# phMeter_v4_2.net
KiCad netlist of a schematic drawn in EAGLE
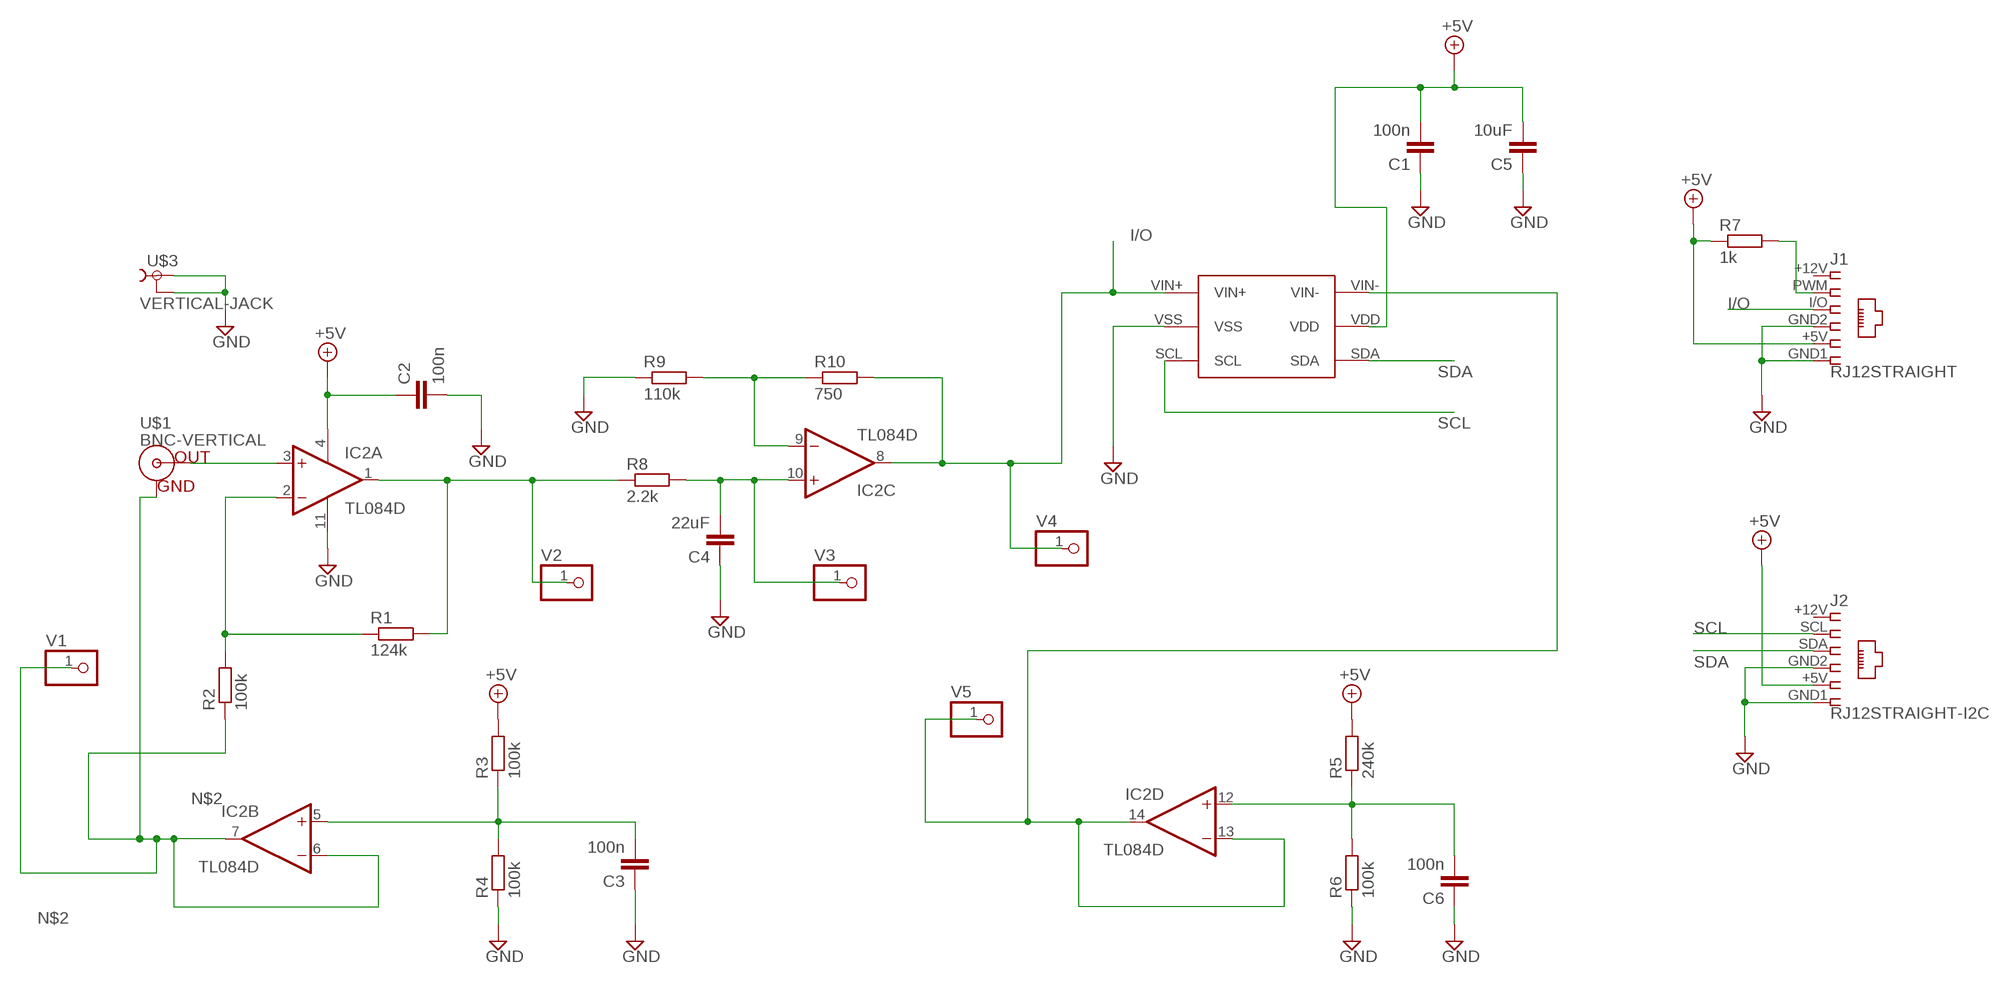
[diagram p0: schematic, sheet 1]

(export (version "E")
  (design (tool "Eeschema 10.0.6"))
  (components
    (comp (ref "C1")
      (value "100n")
      (footprint "eagle-import:C1206")
      (libsource (lib "eagle-import") (part "C-EUC1206"))
    )
    (comp (ref "C2")
      (value "100n")
      (footprint "eagle-import:C1206")
      (libsource (lib "eagle-import") (part "C-EUC1206"))
    )
    (comp (ref "C3")
      (value "100n")
      (footprint "eagle-import:C1206")
      (libsource (lib "eagle-import") (part "C-EUC1206"))
    )
    (comp (ref "C4")
      (value "22uF")
      (footprint "eagle-import:C1206")
      (libsource (lib "eagle-import") (part "C-EUC1206"))
    )
    (comp (ref "C5")
      (value "10uF")
      (footprint "eagle-import:C1206")
      (libsource (lib "eagle-import") (part "C-EUC1206"))
    )
    (comp (ref "C6")
      (value "100n")
      (footprint "eagle-import:C1206")
      (libsource (lib "eagle-import") (part "C-EUC1206"))
    )
    (comp (ref "IC2")
      (value "TL084D")
      (footprint "eagle-import:SO14")
      (libsource (lib "eagle-import") (part "TL084D"))
    )
    (comp (ref "J1")
      (value "RJ12STRAIGHT")
      (footprint "eagle-import:RJ12-STRAIGHT")
      (libsource (lib "eagle-import") (part "RJ12STRAIGHT"))
    )
    (comp (ref "J2")
      (value "RJ12STRAIGHT-I2C")
      (footprint "eagle-import:RJ12-STRAIGHT-I2C")
      (libsource (lib "eagle-import") (part "RJ12STRAIGHT-I2C"))
    )
    (comp (ref "R1")
      (value "124k")
      (footprint "eagle-import:R1206")
      (libsource (lib "eagle-import") (part "R-EU_R1206"))
    )
    (comp (ref "R2")
      (value "100k")
      (footprint "eagle-import:R1206")
      (libsource (lib "eagle-import") (part "R-EU_R1206"))
    )
    (comp (ref "R3")
      (value "100k")
      (footprint "eagle-import:R1206")
      (libsource (lib "eagle-import") (part "R-EU_R1206"))
    )
    (comp (ref "R4")
      (value "100k")
      (footprint "eagle-import:R1206")
      (libsource (lib "eagle-import") (part "R-EU_R1206"))
    )
    (comp (ref "R5")
      (value "240k")
      (footprint "eagle-import:R1206")
      (libsource (lib "eagle-import") (part "R-EU_R1206"))
    )
    (comp (ref "R6")
      (value "100k")
      (footprint "eagle-import:R1206")
      (libsource (lib "eagle-import") (part "R-EU_R1206"))
    )
    (comp (ref "R7")
      (value "1k")
      (footprint "eagle-import:R1206")
      (libsource (lib "eagle-import") (part "R-EU_R1206"))
    )
    (comp (ref "R8")
      (value "2.2k")
      (footprint "eagle-import:R1206")
      (libsource (lib "eagle-import") (part "R-EU_R1206"))
    )
    (comp (ref "R9")
      (value "110k")
      (footprint "eagle-import:R1206")
      (libsource (lib "eagle-import") (part "R-EU_R1206"))
    )
    (comp (ref "R10")
      (value "750")
      (footprint "eagle-import:R1206")
      (libsource (lib "eagle-import") (part "R-EU_R1206"))
    )
    (comp (ref "U$1")
      (value "BNC-VERTICAL")
      (footprint "eagle-import:BNC-VERTICAL")
      (libsource (lib "eagle-import") (part "BNC-VERTICAL"))
    )
    (comp (ref "U$3")
      (value "VERTICAL-JACK")
      (footprint "eagle-import:VERTICAL-JACK")
      (libsource (lib "eagle-import") (part "VERTICAL-JACK"))
    )
    (comp (ref "U$5")
      (value "MCP3425")
      (footprint "eagle-import:SOT-23-6")
      (libsource (lib "eagle-import") (part "MCP3425"))
    )
    (comp (ref "V1")
      (value "PINHD-1X1")
      (footprint "eagle-import:1X01")
      (libsource (lib "eagle-import") (part "PINHD-1X1"))
    )
    (comp (ref "V2")
      (value "PINHD-1X1")
      (footprint "eagle-import:1X01")
      (libsource (lib "eagle-import") (part "PINHD-1X1"))
    )
    (comp (ref "V3")
      (value "PINHD-1X1")
      (footprint "eagle-import:1X01")
      (libsource (lib "eagle-import") (part "PINHD-1X1"))
    )
    (comp (ref "V4")
      (value "PINHD-1X1")
      (footprint "eagle-import:1X01")
      (libsource (lib "eagle-import") (part "PINHD-1X1"))
    )
    (comp (ref "V5")
      (value "PINHD-1X1")
      (footprint "eagle-import:1X01")
      (libsource (lib "eagle-import") (part "PINHD-1X1"))
    )
  )
  (nets
    (net (code "1") (name "+5V") (class "Default")
      (node (ref "C1") (pin "2") (pinfunction "2_2") (pintype "passive"))
      (node (ref "C2") (pin "1") (pinfunction "1_1") (pintype "passive"))
      (node (ref "C5") (pin "2") (pinfunction "2_2") (pintype "passive"))
      (node (ref "IC2") (pin "4") (pinfunction "V+_4") (pintype "power_in"))
      (node (ref "J1") (pin "+5V") (pinfunction "5_+5V") (pintype "bidirectional"))
      (node (ref "J2") (pin "+5V") (pinfunction "5_+5V") (pintype "bidirectional"))
      (node (ref "R3") (pin "2") (pinfunction "2_2") (pintype "passive"))
      (node (ref "R5") (pin "2") (pinfunction "2_2") (pintype "passive"))
      (node (ref "R7") (pin "1") (pinfunction "1_1") (pintype "passive"))
      (node (ref "U$5") (pin "VDD") (pinfunction "VDD_VDD") (pintype "bidirectional"))
    )
    (net (code "2") (name "/I{slash}O") (class "Default")
      (node (ref "IC2") (pin "8") (pinfunction "OUT_8") (pintype "output"))
      (node (ref "J1") (pin "I/O") (pinfunction "3_I/O") (pintype "bidirectional"))
      (node (ref "R10") (pin "2") (pinfunction "2_2") (pintype "passive"))
      (node (ref "U$5") (pin "VIN+") (pinfunction "VIN+_VIN+") (pintype "bidirectional"))
      (node (ref "V4") (pin "1") (pinfunction "1_1") (pintype "passive"))
    )
    (net (code "3") (name "/N$2") (class "Default")
      (node (ref "IC2") (pin "6") (pinfunction "-IN_6") (pintype "input"))
      (node (ref "IC2") (pin "7") (pinfunction "OUT_7") (pintype "output"))
      (node (ref "R2") (pin "1") (pinfunction "1_1") (pintype "passive"))
      (node (ref "U$1") (pin "G") (pinfunction "GND_G") (pintype "bidirectional"))
      (node (ref "V1") (pin "1") (pinfunction "1_1") (pintype "passive"))
    )
    (net (code "4") (name "/SCL") (class "Default")
      (node (ref "J2") (pin "SCL") (pinfunction "2_SCL") (pintype "bidirectional"))
      (node (ref "U$5") (pin "SCL") (pinfunction "SCL_SCL") (pintype "bidirectional"))
    )
    (net (code "5") (name "/SDA") (class "Default")
      (node (ref "J2") (pin "SDA") (pinfunction "3_SDA") (pintype "bidirectional"))
      (node (ref "U$5") (pin "SDA") (pinfunction "SDA_SDA") (pintype "bidirectional"))
    )
    (net (code "6") (name "GND") (class "Default")
      (node (ref "C1") (pin "1") (pinfunction "1_1") (pintype "passive"))
      (node (ref "C2") (pin "2") (pinfunction "2_2") (pintype "passive"))
      (node (ref "C3") (pin "1") (pinfunction "1_1") (pintype "passive"))
      (node (ref "C4") (pin "1") (pinfunction "1_1") (pintype "passive"))
      (node (ref "C5") (pin "1") (pinfunction "1_1") (pintype "passive"))
      (node (ref "C6") (pin "1") (pinfunction "1_1") (pintype "passive"))
      (node (ref "IC2") (pin "11") (pinfunction "V-_11") (pintype "power_in"))
      (node (ref "J1") (pin "GND1") (pinfunction "6_GND1") (pintype "bidirectional"))
      (node (ref "J1") (pin "GND2") (pinfunction "4_GND2") (pintype "bidirectional"))
      (node (ref "J2") (pin "GND1") (pinfunction "6_GND1") (pintype "bidirectional"))
      (node (ref "J2") (pin "GND2") (pinfunction "4_GND2") (pintype "bidirectional"))
      (node (ref "R4") (pin "1") (pinfunction "1_1") (pintype "passive"))
      (node (ref "R6") (pin "1") (pinfunction "1_1") (pintype "passive"))
      (node (ref "R9") (pin "1") (pinfunction "1_1") (pintype "passive"))
      (node (ref "U$3") (pin "P$1") (pinfunction "1_P$1") (pintype "passive"))
      (node (ref "U$3") (pin "P$2") (pinfunction "2_P$2") (pintype "passive"))
      (node (ref "U$5") (pin "VSS") (pinfunction "VSS_VSS") (pintype "bidirectional"))
    )
    (net (code "7") (name "Net-(IC2A-+IN)") (class "Default")
      (node (ref "IC2") (pin "3") (pinfunction "+IN_3") (pintype "input"))
      (node (ref "U$1") (pin "S") (pinfunction "OUT_S") (pintype "bidirectional"))
    )
    (net (code "8") (name "Net-(IC2A--IN)") (class "Default")
      (node (ref "IC2") (pin "2") (pinfunction "-IN_2") (pintype "input"))
      (node (ref "R1") (pin "1") (pinfunction "1_1") (pintype "passive"))
      (node (ref "R2") (pin "2") (pinfunction "2_2") (pintype "passive"))
    )
    (net (code "9") (name "Net-(IC2A-OUT)") (class "Default")
      (node (ref "IC2") (pin "1") (pinfunction "OUT_1") (pintype "output"))
      (node (ref "R1") (pin "2") (pinfunction "2_2") (pintype "passive"))
      (node (ref "R8") (pin "1") (pinfunction "1_1") (pintype "passive"))
      (node (ref "V2") (pin "1") (pinfunction "1_1") (pintype "passive"))
    )
    (net (code "10") (name "Net-(IC2B-+IN)") (class "Default")
      (node (ref "C3") (pin "2") (pinfunction "2_2") (pintype "passive"))
      (node (ref "IC2") (pin "5") (pinfunction "+IN_5") (pintype "input"))
      (node (ref "R3") (pin "1") (pinfunction "1_1") (pintype "passive"))
      (node (ref "R4") (pin "2") (pinfunction "2_2") (pintype "passive"))
    )
    (net (code "11") (name "Net-(IC2C-+IN)") (class "Default")
      (node (ref "C4") (pin "2") (pinfunction "2_2") (pintype "passive"))
      (node (ref "IC2") (pin "10") (pinfunction "+IN_10") (pintype "input"))
      (node (ref "R8") (pin "2") (pinfunction "2_2") (pintype "passive"))
      (node (ref "V3") (pin "1") (pinfunction "1_1") (pintype "passive"))
    )
    (net (code "12") (name "Net-(IC2C--IN)") (class "Default")
      (node (ref "IC2") (pin "9") (pinfunction "-IN_9") (pintype "input"))
      (node (ref "R10") (pin "1") (pinfunction "1_1") (pintype "passive"))
      (node (ref "R9") (pin "2") (pinfunction "2_2") (pintype "passive"))
    )
    (net (code "13") (name "Net-(IC2D-+IN)") (class "Default")
      (node (ref "C6") (pin "2") (pinfunction "2_2") (pintype "passive"))
      (node (ref "IC2") (pin "12") (pinfunction "+IN_12") (pintype "input"))
      (node (ref "R5") (pin "1") (pinfunction "1_1") (pintype "passive"))
      (node (ref "R6") (pin "2") (pinfunction "2_2") (pintype "passive"))
    )
    (net (code "14") (name "Net-(IC2D--IN)") (class "Default")
      (node (ref "IC2") (pin "13") (pinfunction "-IN_13") (pintype "input"))
      (node (ref "IC2") (pin "14") (pinfunction "OUT_14") (pintype "output"))
      (node (ref "U$5") (pin "VIN-") (pinfunction "VIN-_VIN-") (pintype "bidirectional"))
      (node (ref "V5") (pin "1") (pinfunction "1_1") (pintype "passive"))
    )
    (net (code "15") (name "Net-(J1-2)") (class "Default")
      (node (ref "J1") (pin "PWM") (pinfunction "2_PWM") (pintype "bidirectional"))
      (node (ref "R7") (pin "2") (pinfunction "2_2") (pintype "passive"))
    )
    (net (code "16") (name "unconnected-(J1-1-Pad+12V)") (class "Default")
      (node (ref "J1") (pin "+12V") (pinfunction "1_+12V") (pintype "bidirectional"))
    )
    (net (code "17") (name "unconnected-(J2-1-Pad+12V)") (class "Default")
      (node (ref "J2") (pin "+12V") (pinfunction "1_+12V") (pintype "bidirectional"))
    )
  )
)
